# cpu.net
KiCad netlist of a schematic drawn in Altium Designer
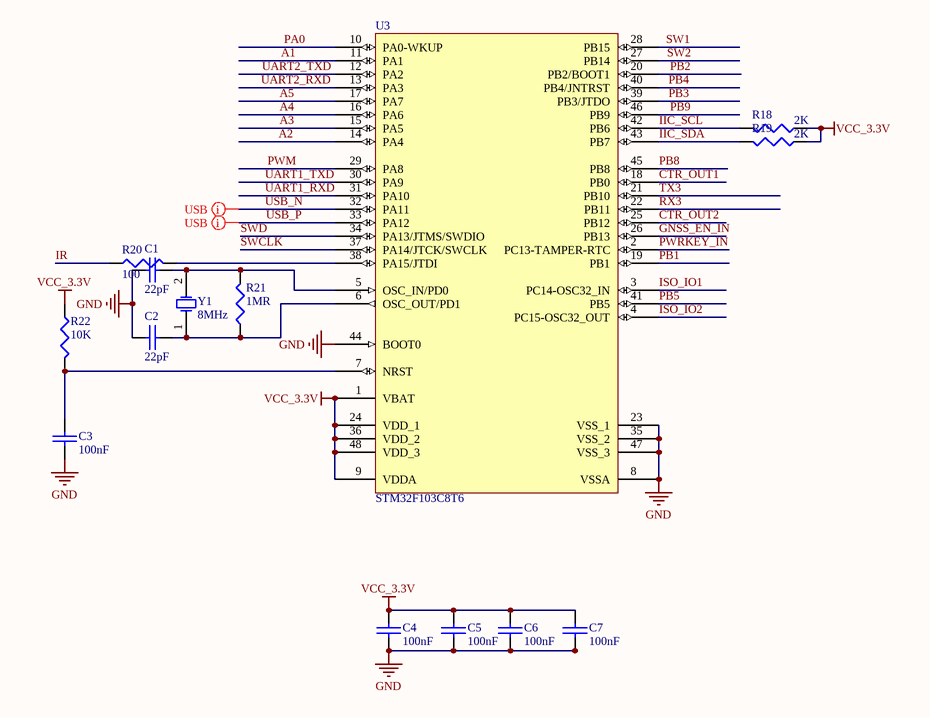
[diagram p0: cpu.SchDoc]

(export (version "E")
  (design (tool "Eeschema 10.0.6"))
  (components
    (comp (ref "C1")
      (value "22pF")
      (footprint "0402C")
      (description "Capacitor")
      (libsource (lib "SM") (part "CAP"))
    )
    (comp (ref "C2")
      (value "22pF")
      (footprint "0402C")
      (description "Capacitor")
      (libsource (lib "SM") (part "CAP"))
    )
    (comp (ref "C3")
      (value "100nF")
      (footprint "0402C")
      (description "Capacitor")
      (libsource (lib "SM") (part "CAP"))
    )
    (comp (ref "C4")
      (value "100nF")
      (footprint "0402C")
      (description "Capacitor")
      (libsource (lib "SM") (part "CAP"))
    )
    (comp (ref "C5")
      (value "100nF")
      (footprint "0402C")
      (description "Capacitor")
      (libsource (lib "SM") (part "CAP"))
    )
    (comp (ref "C6")
      (value "100nF")
      (footprint "0402C")
      (description "Capacitor")
      (libsource (lib "SM") (part "CAP"))
    )
    (comp (ref "C7")
      (value "100nF")
      (footprint "0402C")
      (description "Capacitor")
      (libsource (lib "SM") (part "CAP"))
    )
    (comp (ref "R18")
      (value "2K")
      (footprint "0402R")
      (description "Resistor")
      (fields (field (name "PUBLISHER") "Altium Limited"))
      (libsource (lib "SM") (part "Res3"))
    )
    (comp (ref "R19")
      (value "2K")
      (footprint "0402R")
      (description "Resistor")
      (fields (field (name "PUBLISHER") "Altium Limited"))
      (libsource (lib "SM") (part "Res3"))
    )
    (comp (ref "R20")
      (value "100")
      (footprint "0402R")
      (description "Resistor")
      (fields (field (name "PUBLISHER") "Altium Limited"))
      (libsource (lib "SM") (part "Res3"))
    )
    (comp (ref "R21")
      (value "1MR")
      (footprint "0402R")
      (description "Resistor")
      (fields (field (name "PUBLISHER") "Altium Limited"))
      (libsource (lib "SM") (part "Res3"))
    )
    (comp (ref "R22")
      (value "10K")
      (footprint "0402R")
      (description "Resistor")
      (fields (field (name "PUBLISHER") "Altium Limited"))
      (libsource (lib "SM") (part "Res3"))
    )
    (comp (ref "U3")
      (value "STM32F103C8T6")
      (footprint "TQFP-48")
      (description "STM32 ARM-based 32-bit MCU with 64 Kbytes Flash, 48-pin LQFP, Industrial Temperature")
      (fields (field (name "PUBLISHER") "Altium Limited"))
      (libsource (lib "ST Microcontroller 32-Bit STM32") (part "STM32F103C8T6"))
    )
    (comp (ref "Y1")
      (value "8MHz")
      (footprint "CRAY_5032")
      (description "Crystal Oscillator")
      (fields (field (name "PUBLISHER") "Altium Limited"))
      (libsource (lib "Miscellaneous Devices") (part "XTAL"))
    )
  )
  (nets
    (net (code "1") (name "/A1") (class "Default")
      (node (ref "U3") (pin "11") (pinfunction "PA1_11") (pintype "bidirectional"))
    )
    (net (code "2") (name "/A2") (class "Default")
      (node (ref "U3") (pin "14") (pinfunction "PA4_14") (pintype "bidirectional"))
    )
    (net (code "3") (name "/A3") (class "Default")
      (node (ref "U3") (pin "15") (pinfunction "PA5_15") (pintype "bidirectional"))
    )
    (net (code "4") (name "/A4") (class "Default")
      (node (ref "U3") (pin "16") (pinfunction "PA6_16") (pintype "bidirectional"))
    )
    (net (code "5") (name "/A5") (class "Default")
      (node (ref "U3") (pin "17") (pinfunction "PA7_17") (pintype "bidirectional"))
    )
    (net (code "6") (name "/CTR_OUT1") (class "Default")
      (node (ref "U3") (pin "18") (pinfunction "PB0_18") (pintype "bidirectional"))
    )
    (net (code "7") (name "/CTR_OUT2") (class "Default")
      (node (ref "U3") (pin "25") (pinfunction "PB12_25") (pintype "bidirectional"))
    )
    (net (code "8") (name "/GNSS_EN_IN") (class "Default")
      (node (ref "U3") (pin "26") (pinfunction "PB13_26") (pintype "bidirectional"))
    )
    (net (code "9") (name "/IIC_SCL") (class "Default")
      (node (ref "R18") (pin "2") (pinfunction "2_2") (pintype "passive"))
      (node (ref "U3") (pin "42") (pinfunction "PB6_42") (pintype "bidirectional"))
    )
    (net (code "10") (name "/IIC_SDA") (class "Default")
      (node (ref "R19") (pin "2") (pinfunction "2_2") (pintype "passive"))
      (node (ref "U3") (pin "43") (pinfunction "PB7_43") (pintype "bidirectional"))
    )
    (net (code "11") (name "/IR") (class "Default")
      (node (ref "R20") (pin "1") (pinfunction "1_1") (pintype "passive"))
    )
    (net (code "12") (name "/ISO_IO1") (class "Default")
      (node (ref "U3") (pin "3") (pinfunction "PC14-OSC32_IN_3") (pintype "bidirectional"))
    )
    (net (code "13") (name "/ISO_IO2") (class "Default")
      (node (ref "U3") (pin "4") (pinfunction "PC15-OSC32_OUT_4") (pintype "bidirectional"))
    )
    (net (code "14") (name "/PA0") (class "Default")
      (node (ref "U3") (pin "10") (pinfunction "PA0-WKUP_10") (pintype "bidirectional"))
    )
    (net (code "15") (name "/PB1") (class "Default")
      (node (ref "U3") (pin "19") (pinfunction "PB1_19") (pintype "bidirectional"))
    )
    (net (code "16") (name "/PB2") (class "Default")
      (node (ref "U3") (pin "20") (pinfunction "PB2/BOOT1_20") (pintype "bidirectional"))
    )
    (net (code "17") (name "/PB3") (class "Default")
      (node (ref "U3") (pin "39") (pinfunction "PB3/JTDO_39") (pintype "bidirectional"))
    )
    (net (code "18") (name "/PB4") (class "Default")
      (node (ref "U3") (pin "40") (pinfunction "PB4/JNTRST_40") (pintype "bidirectional"))
    )
    (net (code "19") (name "/PB5") (class "Default")
      (node (ref "U3") (pin "41") (pinfunction "PB5_41") (pintype "bidirectional"))
    )
    (net (code "20") (name "/PB8") (class "Default")
      (node (ref "U3") (pin "45") (pinfunction "PB8_45") (pintype "bidirectional"))
    )
    (net (code "21") (name "/PB9") (class "Default")
      (node (ref "U3") (pin "46") (pinfunction "PB9_46") (pintype "bidirectional"))
    )
    (net (code "22") (name "/PWM") (class "Default")
      (node (ref "U3") (pin "29") (pinfunction "PA8_29") (pintype "bidirectional"))
    )
    (net (code "23") (name "/PWRKEY_IN") (class "Default")
      (node (ref "U3") (pin "2") (pinfunction "PC13-TAMPER-RTC_2") (pintype "bidirectional"))
    )
    (net (code "24") (name "/RX3") (class "Default")
      (node (ref "U3") (pin "22") (pinfunction "PB11_22") (pintype "bidirectional"))
    )
    (net (code "25") (name "/SW1") (class "Default")
      (node (ref "U3") (pin "28") (pinfunction "PB15_28") (pintype "bidirectional"))
    )
    (net (code "26") (name "/SW2") (class "Default")
      (node (ref "U3") (pin "27") (pinfunction "PB14_27") (pintype "bidirectional"))
    )
    (net (code "27") (name "/SWCLK") (class "Default")
      (node (ref "U3") (pin "37") (pinfunction "PA14/JTCK/SWCLK_37") (pintype "bidirectional"))
    )
    (net (code "28") (name "/SWD") (class "Default")
      (node (ref "U3") (pin "34") (pinfunction "PA13/JTMS/SWDIO_34") (pintype "bidirectional"))
    )
    (net (code "29") (name "/TX3") (class "Default")
      (node (ref "U3") (pin "21") (pinfunction "PB10_21") (pintype "bidirectional"))
    )
    (net (code "30") (name "/UART1_RXD") (class "Default")
      (node (ref "U3") (pin "31") (pinfunction "PA10_31") (pintype "bidirectional"))
    )
    (net (code "31") (name "/UART1_TXD") (class "Default")
      (node (ref "U3") (pin "30") (pinfunction "PA9_30") (pintype "bidirectional"))
    )
    (net (code "32") (name "/UART2_RXD") (class "Default")
      (node (ref "U3") (pin "13") (pinfunction "PA3_13") (pintype "bidirectional"))
    )
    (net (code "33") (name "/UART2_TXD") (class "Default")
      (node (ref "U3") (pin "12") (pinfunction "PA2_12") (pintype "bidirectional"))
    )
    (net (code "34") (name "/USB_N") (class "Default")
      (node (ref "U3") (pin "32") (pinfunction "PA11_32") (pintype "bidirectional"))
    )
    (net (code "35") (name "/USB_P") (class "Default")
      (node (ref "U3") (pin "33") (pinfunction "PA12_33") (pintype "bidirectional"))
    )
    (net (code "36") (name "GND") (class "Default")
      (node (ref "C1") (pin "1") (pinfunction "1_1") (pintype "passive"))
      (node (ref "C2") (pin "1") (pinfunction "1_1") (pintype "passive"))
      (node (ref "C3") (pin "1") (pinfunction "1_1") (pintype "passive"))
      (node (ref "C4") (pin "1") (pinfunction "1_1") (pintype "passive"))
      (node (ref "C5") (pin "1") (pinfunction "1_1") (pintype "passive"))
      (node (ref "C6") (pin "1") (pinfunction "1_1") (pintype "passive"))
      (node (ref "C7") (pin "1") (pinfunction "1_1") (pintype "passive"))
      (node (ref "U3") (pin "23") (pinfunction "VSS_1_23") (pintype "power_in"))
      (node (ref "U3") (pin "35") (pinfunction "VSS_2_35") (pintype "power_in"))
      (node (ref "U3") (pin "44") (pinfunction "BOOT0_44") (pintype "input"))
      (node (ref "U3") (pin "47") (pinfunction "VSS_3_47") (pintype "power_in"))
      (node (ref "U3") (pin "8") (pinfunction "VSSA_8") (pintype "power_in"))
    )
    (net (code "37") (name "Net-(U3-NRST)") (class "Default")
      (node (ref "C3") (pin "2") (pinfunction "2_2") (pintype "passive"))
      (node (ref "R22") (pin "2") (pinfunction "2_2") (pintype "passive"))
      (node (ref "U3") (pin "7") (pinfunction "NRST_7") (pintype "bidirectional"))
    )
    (net (code "38") (name "Net-(U3-OSC_IN{slash}PD0)") (class "Default")
      (node (ref "C1") (pin "2") (pinfunction "2_2") (pintype "passive"))
      (node (ref "R21") (pin "2") (pinfunction "2_2") (pintype "passive"))
      (node (ref "U3") (pin "5") (pinfunction "OSC_IN/PD0_5") (pintype "input"))
      (node (ref "Y1") (pin "2") (pinfunction "OSC2_2") (pintype "passive"))
    )
    (net (code "39") (name "Net-(U3-OSC_OUT{slash}PD1)") (class "Default")
      (node (ref "C2") (pin "2") (pinfunction "2_2") (pintype "passive"))
      (node (ref "R21") (pin "1") (pinfunction "1_1") (pintype "passive"))
      (node (ref "U3") (pin "6") (pinfunction "OSC_OUT/PD1_6") (pintype "output"))
      (node (ref "Y1") (pin "1") (pinfunction "OSC1_1") (pintype "passive"))
    )
    (net (code "40") (name "Net-(U3-PA15{slash}JTDI)") (class "Default")
      (node (ref "R20") (pin "2") (pinfunction "2_2") (pintype "passive"))
      (node (ref "U3") (pin "38") (pinfunction "PA15/JTDI_38") (pintype "bidirectional"))
    )
    (net (code "41") (name "VCC_3.3V") (class "Default")
      (node (ref "C4") (pin "2") (pinfunction "2_2") (pintype "passive"))
      (node (ref "C5") (pin "2") (pinfunction "2_2") (pintype "passive"))
      (node (ref "C6") (pin "2") (pinfunction "2_2") (pintype "passive"))
      (node (ref "C7") (pin "2") (pinfunction "2_2") (pintype "passive"))
      (node (ref "R18") (pin "1") (pinfunction "1_1") (pintype "passive"))
      (node (ref "R19") (pin "1") (pinfunction "1_1") (pintype "passive"))
      (node (ref "R22") (pin "1") (pinfunction "1_1") (pintype "passive"))
      (node (ref "U3") (pin "1") (pinfunction "VBAT_1") (pintype "power_in"))
      (node (ref "U3") (pin "24") (pinfunction "VDD_1_24") (pintype "power_in"))
      (node (ref "U3") (pin "36") (pinfunction "VDD_2_36") (pintype "power_in"))
      (node (ref "U3") (pin "48") (pinfunction "VDD_3_48") (pintype "power_in"))
      (node (ref "U3") (pin "9") (pinfunction "VDDA_9") (pintype "power_in"))
    )
  )
)
